# SenseBorgHAT.net
KiCad netlist of a schematic drawn in EAGLE
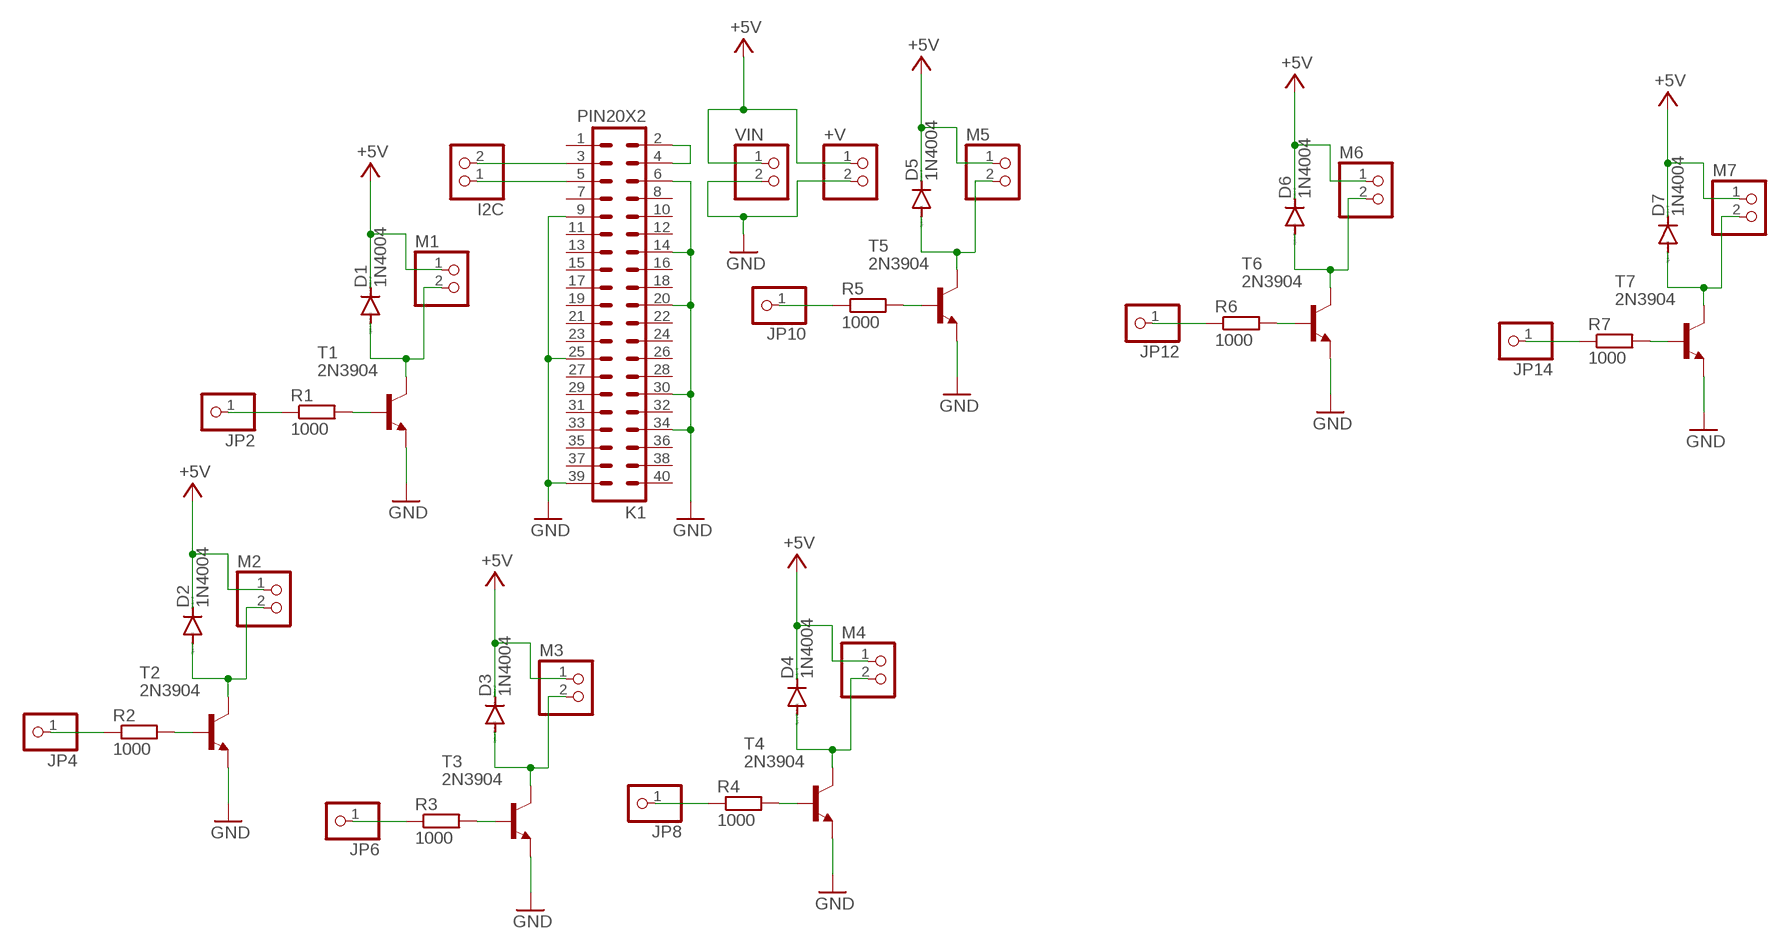
[diagram p0: schematic, sheet 1, part 1 of 2]
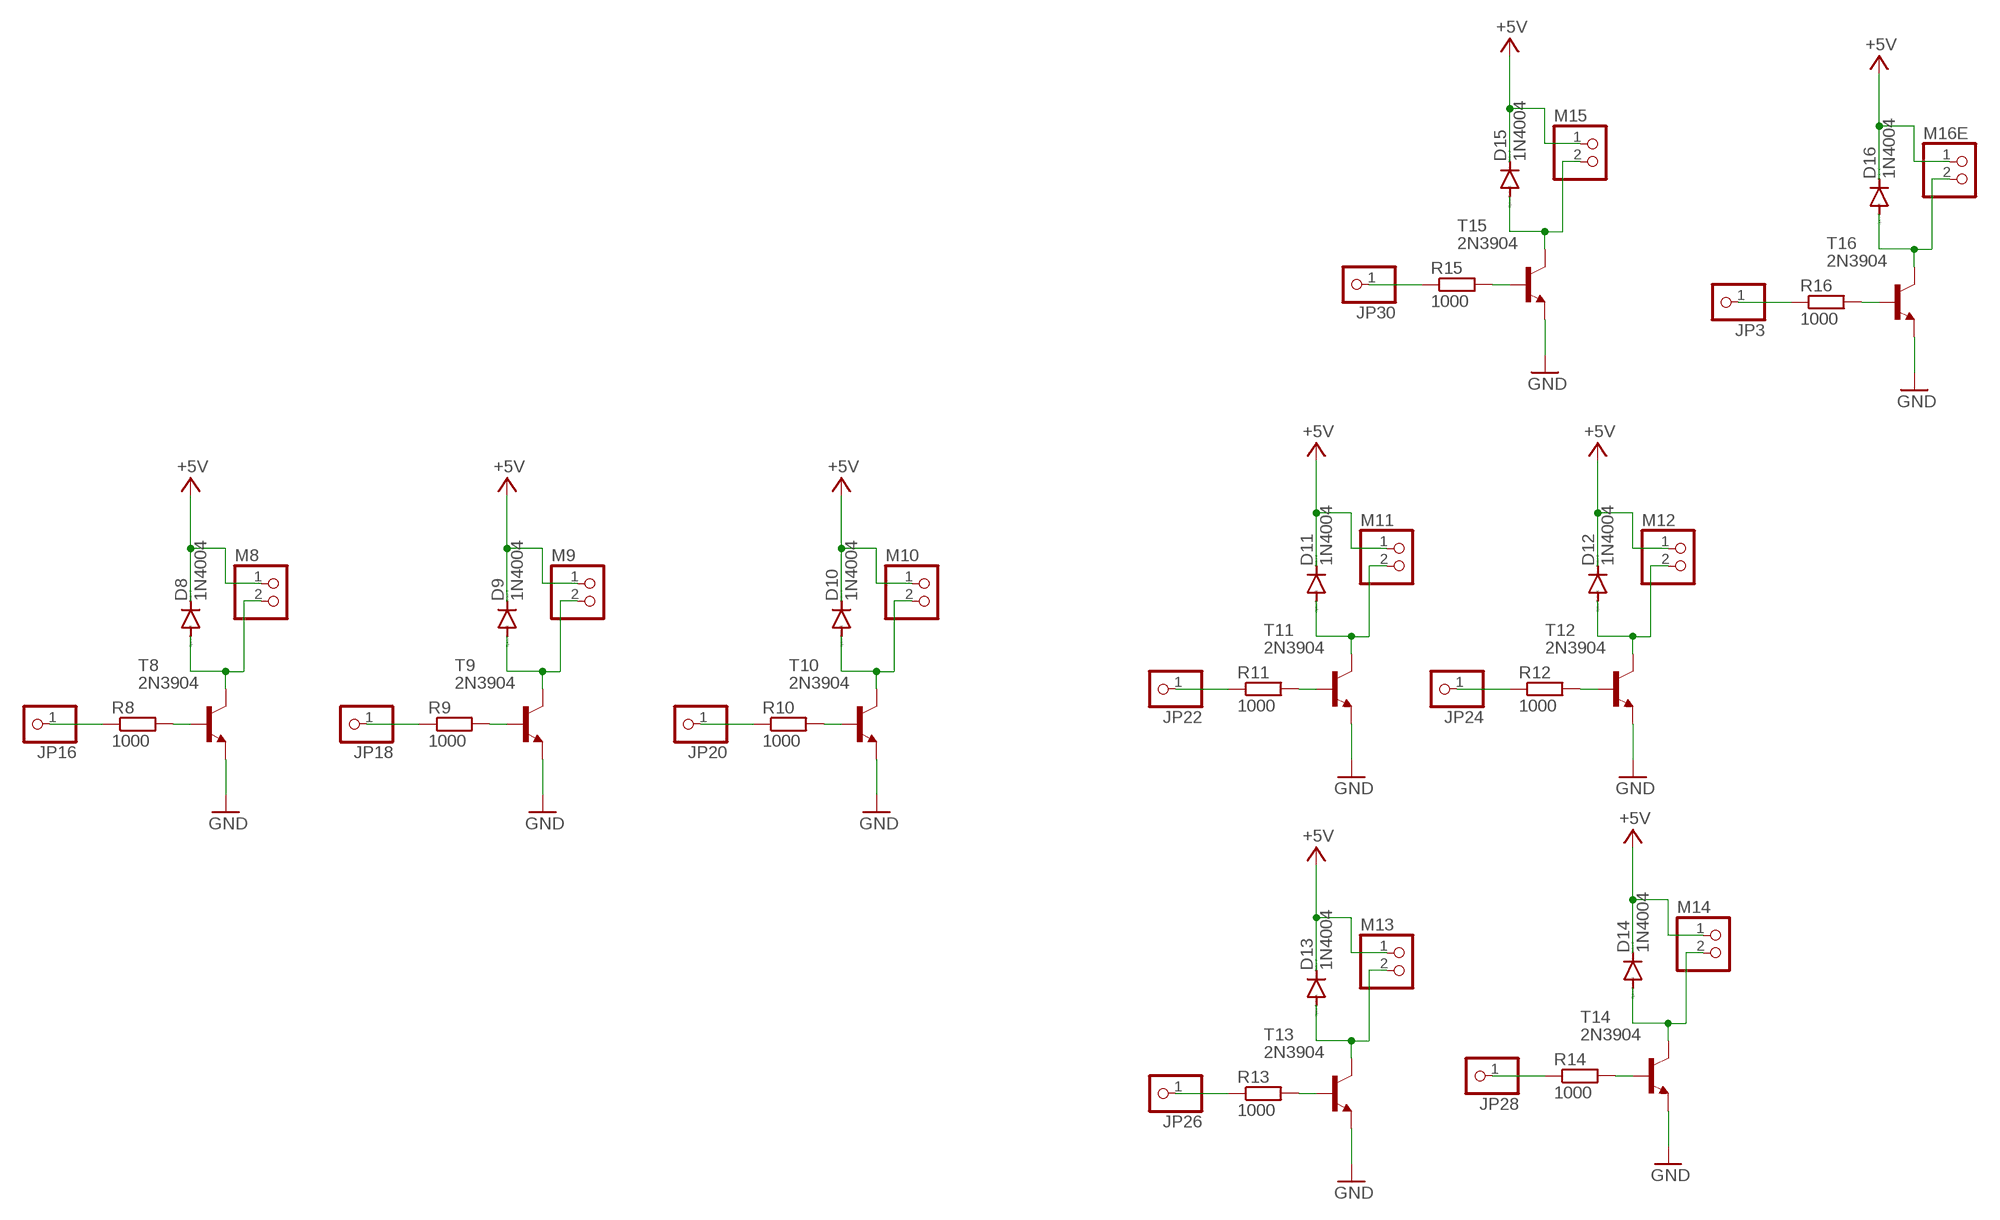
[diagram p1: schematic, sheet 1, part 2 of 2]

(export (version "E")
  (design (tool "Eeschema 10.0.6"))
  (components
    (comp (ref "+V")
      (value "PINHD-1X2")
      (footprint "eagle-import:1X02")
      (libsource (lib "eagle-import") (part "PINHD-1X2"))
    )
    (comp (ref "D1")
      (value "1N4004")
      (footprint "eagle-import:DO41-10")
      (libsource (lib "eagle-import") (part "1N4004"))
    )
    (comp (ref "D2")
      (value "1N4004")
      (footprint "eagle-import:DO41-10")
      (libsource (lib "eagle-import") (part "1N4004"))
    )
    (comp (ref "D3")
      (value "1N4004")
      (footprint "eagle-import:DO41-10")
      (libsource (lib "eagle-import") (part "1N4004"))
    )
    (comp (ref "D4")
      (value "1N4004")
      (footprint "eagle-import:DO41-10")
      (libsource (lib "eagle-import") (part "1N4004"))
    )
    (comp (ref "D5")
      (value "1N4004")
      (footprint "eagle-import:DO41-10")
      (libsource (lib "eagle-import") (part "1N4004"))
    )
    (comp (ref "D6")
      (value "1N4004")
      (footprint "eagle-import:DO41-10")
      (libsource (lib "eagle-import") (part "1N4004"))
    )
    (comp (ref "D7")
      (value "1N4004")
      (footprint "eagle-import:DO41-10")
      (libsource (lib "eagle-import") (part "1N4004"))
    )
    (comp (ref "D8")
      (value "1N4004")
      (footprint "eagle-import:DO41-10")
      (libsource (lib "eagle-import") (part "1N4004"))
    )
    (comp (ref "D9")
      (value "1N4004")
      (footprint "eagle-import:DO41-10")
      (libsource (lib "eagle-import") (part "1N4004"))
    )
    (comp (ref "D10")
      (value "1N4004")
      (footprint "eagle-import:DO41-10")
      (libsource (lib "eagle-import") (part "1N4004"))
    )
    (comp (ref "D11")
      (value "1N4004")
      (footprint "eagle-import:DO41-10")
      (libsource (lib "eagle-import") (part "1N4004"))
    )
    (comp (ref "D12")
      (value "1N4004")
      (footprint "eagle-import:DO41-10")
      (libsource (lib "eagle-import") (part "1N4004"))
    )
    (comp (ref "D13")
      (value "1N4004")
      (footprint "eagle-import:DO41-10")
      (libsource (lib "eagle-import") (part "1N4004"))
    )
    (comp (ref "D14")
      (value "1N4004")
      (footprint "eagle-import:DO41-10")
      (libsource (lib "eagle-import") (part "1N4004"))
    )
    (comp (ref "D15")
      (value "1N4004")
      (footprint "eagle-import:DO41-10")
      (libsource (lib "eagle-import") (part "1N4004"))
    )
    (comp (ref "D16")
      (value "1N4004")
      (footprint "eagle-import:DO41-10")
      (libsource (lib "eagle-import") (part "1N4004"))
    )
    (comp (ref "I2C")
      (value "PINHD-1X2")
      (footprint "eagle-import:1X02")
      (libsource (lib "eagle-import") (part "PINHD-1X2"))
    )
    (comp (ref "JP2")
      (value "PINHD-1X1")
      (footprint "eagle-import:1X01")
      (libsource (lib "eagle-import") (part "PINHD-1X1"))
    )
    (comp (ref "JP3")
      (value "PINHD-1X1")
      (footprint "eagle-import:1X01")
      (libsource (lib "eagle-import") (part "PINHD-1X1"))
    )
    (comp (ref "JP4")
      (value "PINHD-1X1")
      (footprint "eagle-import:1X01")
      (libsource (lib "eagle-import") (part "PINHD-1X1"))
    )
    (comp (ref "JP6")
      (value "PINHD-1X1")
      (footprint "eagle-import:1X01")
      (libsource (lib "eagle-import") (part "PINHD-1X1"))
    )
    (comp (ref "JP8")
      (value "PINHD-1X1")
      (footprint "eagle-import:1X01")
      (libsource (lib "eagle-import") (part "PINHD-1X1"))
    )
    (comp (ref "JP10")
      (value "PINHD-1X1")
      (footprint "eagle-import:1X01")
      (libsource (lib "eagle-import") (part "PINHD-1X1"))
    )
    (comp (ref "JP12")
      (value "PINHD-1X1")
      (footprint "eagle-import:1X01")
      (libsource (lib "eagle-import") (part "PINHD-1X1"))
    )
    (comp (ref "JP14")
      (value "PINHD-1X1")
      (footprint "eagle-import:1X01")
      (libsource (lib "eagle-import") (part "PINHD-1X1"))
    )
    (comp (ref "JP16")
      (value "PINHD-1X1")
      (footprint "eagle-import:1X01")
      (libsource (lib "eagle-import") (part "PINHD-1X1"))
    )
    (comp (ref "JP18")
      (value "PINHD-1X1")
      (footprint "eagle-import:1X01")
      (libsource (lib "eagle-import") (part "PINHD-1X1"))
    )
    (comp (ref "JP20")
      (value "PINHD-1X1")
      (footprint "eagle-import:1X01")
      (libsource (lib "eagle-import") (part "PINHD-1X1"))
    )
    (comp (ref "JP22")
      (value "PINHD-1X1")
      (footprint "eagle-import:1X01")
      (libsource (lib "eagle-import") (part "PINHD-1X1"))
    )
    (comp (ref "JP24")
      (value "PINHD-1X1")
      (footprint "eagle-import:1X01")
      (libsource (lib "eagle-import") (part "PINHD-1X1"))
    )
    (comp (ref "JP26")
      (value "PINHD-1X1")
      (footprint "eagle-import:1X01")
      (libsource (lib "eagle-import") (part "PINHD-1X1"))
    )
    (comp (ref "JP28")
      (value "PINHD-1X1")
      (footprint "eagle-import:1X01")
      (libsource (lib "eagle-import") (part "PINHD-1X1"))
    )
    (comp (ref "JP30")
      (value "PINHD-1X1")
      (footprint "eagle-import:1X01")
      (libsource (lib "eagle-import") (part "PINHD-1X1"))
    )
    (comp (ref "K1")
      (value "PIN20X2")
      (footprint "eagle-import:PIN_20X2")
      (libsource (lib "eagle-import") (part "PIN20X2"))
    )
    (comp (ref "M1")
      (value "PINHD-1X2")
      (footprint "eagle-import:1X02")
      (libsource (lib "eagle-import") (part "PINHD-1X2"))
    )
    (comp (ref "M2")
      (value "PINHD-1X2")
      (footprint "eagle-import:1X02")
      (libsource (lib "eagle-import") (part "PINHD-1X2"))
    )
    (comp (ref "M3")
      (value "PINHD-1X2")
      (footprint "eagle-import:1X02")
      (libsource (lib "eagle-import") (part "PINHD-1X2"))
    )
    (comp (ref "M4")
      (value "PINHD-1X2")
      (footprint "eagle-import:1X02")
      (libsource (lib "eagle-import") (part "PINHD-1X2"))
    )
    (comp (ref "M5")
      (value "PINHD-1X2")
      (footprint "eagle-import:1X02")
      (libsource (lib "eagle-import") (part "PINHD-1X2"))
    )
    (comp (ref "M6")
      (value "PINHD-1X2")
      (footprint "eagle-import:1X02")
      (libsource (lib "eagle-import") (part "PINHD-1X2"))
    )
    (comp (ref "M7")
      (value "PINHD-1X2")
      (footprint "eagle-import:1X02")
      (libsource (lib "eagle-import") (part "PINHD-1X2"))
    )
    (comp (ref "M8")
      (value "PINHD-1X2")
      (footprint "eagle-import:1X02")
      (libsource (lib "eagle-import") (part "PINHD-1X2"))
    )
    (comp (ref "M9")
      (value "PINHD-1X2")
      (footprint "eagle-import:1X02")
      (libsource (lib "eagle-import") (part "PINHD-1X2"))
    )
    (comp (ref "M10")
      (value "PINHD-1X2")
      (footprint "eagle-import:1X02")
      (libsource (lib "eagle-import") (part "PINHD-1X2"))
    )
    (comp (ref "M11")
      (value "PINHD-1X2")
      (footprint "eagle-import:1X02")
      (libsource (lib "eagle-import") (part "PINHD-1X2"))
    )
    (comp (ref "M12")
      (value "PINHD-1X2")
      (footprint "eagle-import:1X02")
      (libsource (lib "eagle-import") (part "PINHD-1X2"))
    )
    (comp (ref "M13")
      (value "PINHD-1X2")
      (footprint "eagle-import:1X02")
      (libsource (lib "eagle-import") (part "PINHD-1X2"))
    )
    (comp (ref "M14")
      (value "PINHD-1X2")
      (footprint "eagle-import:1X02")
      (libsource (lib "eagle-import") (part "PINHD-1X2"))
    )
    (comp (ref "M15")
      (value "PINHD-1X2")
      (footprint "eagle-import:1X02")
      (libsource (lib "eagle-import") (part "PINHD-1X2"))
    )
    (comp (ref "M16E")
      (value "PINHD-1X2")
      (footprint "eagle-import:1X02")
      (libsource (lib "eagle-import") (part "PINHD-1X2"))
    )
    (comp (ref "R1")
      (value "1000")
      (footprint "eagle-import:0207_10")
      (libsource (lib "eagle-import") (part "R-EU_0207/10"))
    )
    (comp (ref "R2")
      (value "1000")
      (footprint "eagle-import:0207_10")
      (libsource (lib "eagle-import") (part "R-EU_0207/10"))
    )
    (comp (ref "R3")
      (value "1000")
      (footprint "eagle-import:0207_10")
      (libsource (lib "eagle-import") (part "R-EU_0207/10"))
    )
    (comp (ref "R4")
      (value "1000")
      (footprint "eagle-import:0207_10")
      (libsource (lib "eagle-import") (part "R-EU_0207/10"))
    )
    (comp (ref "R5")
      (value "1000")
      (footprint "eagle-import:0207_10")
      (libsource (lib "eagle-import") (part "R-EU_0207/10"))
    )
    (comp (ref "R6")
      (value "1000")
      (footprint "eagle-import:0207_10")
      (libsource (lib "eagle-import") (part "R-EU_0207/10"))
    )
    (comp (ref "R7")
      (value "1000")
      (footprint "eagle-import:0207_10")
      (libsource (lib "eagle-import") (part "R-EU_0207/10"))
    )
    (comp (ref "R8")
      (value "1000")
      (footprint "eagle-import:0207_10")
      (libsource (lib "eagle-import") (part "R-EU_0207/10"))
    )
    (comp (ref "R9")
      (value "1000")
      (footprint "eagle-import:0207_10")
      (libsource (lib "eagle-import") (part "R-EU_0207/10"))
    )
    (comp (ref "R10")
      (value "1000")
      (footprint "eagle-import:0207_10")
      (libsource (lib "eagle-import") (part "R-EU_0207/10"))
    )
    (comp (ref "R11")
      (value "1000")
      (footprint "eagle-import:0207_10")
      (libsource (lib "eagle-import") (part "R-EU_0207/10"))
    )
    (comp (ref "R12")
      (value "1000")
      (footprint "eagle-import:0207_10")
      (libsource (lib "eagle-import") (part "R-EU_0207/10"))
    )
    (comp (ref "R13")
      (value "1000")
      (footprint "eagle-import:0207_10")
      (libsource (lib "eagle-import") (part "R-EU_0207/10"))
    )
    (comp (ref "R14")
      (value "1000")
      (footprint "eagle-import:0207_10")
      (libsource (lib "eagle-import") (part "R-EU_0207/10"))
    )
    (comp (ref "R15")
      (value "1000")
      (footprint "eagle-import:0207_10")
      (libsource (lib "eagle-import") (part "R-EU_0207/10"))
    )
    (comp (ref "R16")
      (value "1000")
      (footprint "eagle-import:0207_10")
      (libsource (lib "eagle-import") (part "R-EU_0207/10"))
    )
    (comp (ref "T1")
      (value "2N3904")
      (footprint "eagle-import:TO92")
      (libsource (lib "eagle-import") (part "2N3904"))
    )
    (comp (ref "T2")
      (value "2N3904")
      (footprint "eagle-import:TO92")
      (libsource (lib "eagle-import") (part "2N3904"))
    )
    (comp (ref "T3")
      (value "2N3904")
      (footprint "eagle-import:TO92")
      (libsource (lib "eagle-import") (part "2N3904"))
    )
    (comp (ref "T4")
      (value "2N3904")
      (footprint "eagle-import:TO92")
      (libsource (lib "eagle-import") (part "2N3904"))
    )
    (comp (ref "T5")
      (value "2N3904")
      (footprint "eagle-import:TO92")
      (libsource (lib "eagle-import") (part "2N3904"))
    )
    (comp (ref "T6")
      (value "2N3904")
      (footprint "eagle-import:TO92")
      (libsource (lib "eagle-import") (part "2N3904"))
    )
    (comp (ref "T7")
      (value "2N3904")
      (footprint "eagle-import:TO92")
      (libsource (lib "eagle-import") (part "2N3904"))
    )
    (comp (ref "T8")
      (value "2N3904")
      (footprint "eagle-import:TO92")
      (libsource (lib "eagle-import") (part "2N3904"))
    )
    (comp (ref "T9")
      (value "2N3904")
      (footprint "eagle-import:TO92")
      (libsource (lib "eagle-import") (part "2N3904"))
    )
    (comp (ref "T10")
      (value "2N3904")
      (footprint "eagle-import:TO92")
      (libsource (lib "eagle-import") (part "2N3904"))
    )
    (comp (ref "T11")
      (value "2N3904")
      (footprint "eagle-import:TO92")
      (libsource (lib "eagle-import") (part "2N3904"))
    )
    (comp (ref "T12")
      (value "2N3904")
      (footprint "eagle-import:TO92")
      (libsource (lib "eagle-import") (part "2N3904"))
    )
    (comp (ref "T13")
      (value "2N3904")
      (footprint "eagle-import:TO92")
      (libsource (lib "eagle-import") (part "2N3904"))
    )
    (comp (ref "T14")
      (value "2N3904")
      (footprint "eagle-import:TO92")
      (libsource (lib "eagle-import") (part "2N3904"))
    )
    (comp (ref "T15")
      (value "2N3904")
      (footprint "eagle-import:TO92")
      (libsource (lib "eagle-import") (part "2N3904"))
    )
    (comp (ref "T16")
      (value "2N3904")
      (footprint "eagle-import:TO92")
      (libsource (lib "eagle-import") (part "2N3904"))
    )
    (comp (ref "VIN")
      (value "PINHD-1X2")
      (footprint "eagle-import:1X02")
      (libsource (lib "eagle-import") (part "PINHD-1X2"))
    )
  )
  (nets
    (net (code "1") (name "+5V") (class "Default")
      (node (ref "+V") (pin "1") (pinfunction "1_1") (pintype "passive"))
      (node (ref "D1") (pin "C") (pinfunction "C_C") (pintype "passive"))
      (node (ref "D10") (pin "C") (pinfunction "C_C") (pintype "passive"))
      (node (ref "D11") (pin "C") (pinfunction "C_C") (pintype "passive"))
      (node (ref "D12") (pin "C") (pinfunction "C_C") (pintype "passive"))
      (node (ref "D13") (pin "C") (pinfunction "C_C") (pintype "passive"))
      (node (ref "D14") (pin "C") (pinfunction "C_C") (pintype "passive"))
      (node (ref "D15") (pin "C") (pinfunction "C_C") (pintype "passive"))
      (node (ref "D16") (pin "C") (pinfunction "C_C") (pintype "passive"))
      (node (ref "D2") (pin "C") (pinfunction "C_C") (pintype "passive"))
      (node (ref "D3") (pin "C") (pinfunction "C_C") (pintype "passive"))
      (node (ref "D4") (pin "C") (pinfunction "C_C") (pintype "passive"))
      (node (ref "D5") (pin "C") (pinfunction "C_C") (pintype "passive"))
      (node (ref "D6") (pin "C") (pinfunction "C_C") (pintype "passive"))
      (node (ref "D7") (pin "C") (pinfunction "C_C") (pintype "passive"))
      (node (ref "D8") (pin "C") (pinfunction "C_C") (pintype "passive"))
      (node (ref "D9") (pin "C") (pinfunction "C_C") (pintype "passive"))
      (node (ref "M1") (pin "1") (pinfunction "1_1") (pintype "passive"))
      (node (ref "M10") (pin "1") (pinfunction "1_1") (pintype "passive"))
      (node (ref "M11") (pin "1") (pinfunction "1_1") (pintype "passive"))
      (node (ref "M12") (pin "1") (pinfunction "1_1") (pintype "passive"))
      (node (ref "M13") (pin "1") (pinfunction "1_1") (pintype "passive"))
      (node (ref "M14") (pin "1") (pinfunction "1_1") (pintype "passive"))
      (node (ref "M15") (pin "1") (pinfunction "1_1") (pintype "passive"))
      (node (ref "M16E") (pin "1") (pinfunction "1_1") (pintype "passive"))
      (node (ref "M2") (pin "1") (pinfunction "1_1") (pintype "passive"))
      (node (ref "M3") (pin "1") (pinfunction "1_1") (pintype "passive"))
      (node (ref "M4") (pin "1") (pinfunction "1_1") (pintype "passive"))
      (node (ref "M5") (pin "1") (pinfunction "1_1") (pintype "passive"))
      (node (ref "M6") (pin "1") (pinfunction "1_1") (pintype "passive"))
      (node (ref "M7") (pin "1") (pinfunction "1_1") (pintype "passive"))
      (node (ref "M8") (pin "1") (pinfunction "1_1") (pintype "passive"))
      (node (ref "M9") (pin "1") (pinfunction "1_1") (pintype "passive"))
      (node (ref "VIN") (pin "1") (pinfunction "1_1") (pintype "passive"))
    )
    (net (code "2") (name "GND") (class "Default")
      (node (ref "+V") (pin "2") (pinfunction "2_2") (pintype "passive"))
      (node (ref "K1") (pin "14") (pinfunction "14_14") (pintype "passive"))
      (node (ref "K1") (pin "20") (pinfunction "20_20") (pintype "passive"))
      (node (ref "K1") (pin "25") (pinfunction "25_25") (pintype "passive"))
      (node (ref "K1") (pin "30") (pinfunction "30_30") (pintype "passive"))
      (node (ref "K1") (pin "34") (pinfunction "34_34") (pintype "passive"))
      (node (ref "K1") (pin "39") (pinfunction "39_39") (pintype "passive"))
      (node (ref "K1") (pin "6") (pinfunction "6_6") (pintype "passive"))
      (node (ref "K1") (pin "9") (pinfunction "9_9") (pintype "passive"))
      (node (ref "T1") (pin "3") (pinfunction "E_3") (pintype "passive"))
      (node (ref "T10") (pin "3") (pinfunction "E_3") (pintype "passive"))
      (node (ref "T11") (pin "3") (pinfunction "E_3") (pintype "passive"))
      (node (ref "T12") (pin "3") (pinfunction "E_3") (pintype "passive"))
      (node (ref "T13") (pin "3") (pinfunction "E_3") (pintype "passive"))
      (node (ref "T14") (pin "3") (pinfunction "E_3") (pintype "passive"))
      (node (ref "T15") (pin "3") (pinfunction "E_3") (pintype "passive"))
      (node (ref "T16") (pin "3") (pinfunction "E_3") (pintype "passive"))
      (node (ref "T2") (pin "3") (pinfunction "E_3") (pintype "passive"))
      (node (ref "T3") (pin "3") (pinfunction "E_3") (pintype "passive"))
      (node (ref "T4") (pin "3") (pinfunction "E_3") (pintype "passive"))
      (node (ref "T5") (pin "3") (pinfunction "E_3") (pintype "passive"))
      (node (ref "T6") (pin "3") (pinfunction "E_3") (pintype "passive"))
      (node (ref "T7") (pin "3") (pinfunction "E_3") (pintype "passive"))
      (node (ref "T8") (pin "3") (pinfunction "E_3") (pintype "passive"))
      (node (ref "T9") (pin "3") (pinfunction "E_3") (pintype "passive"))
      (node (ref "VIN") (pin "2") (pinfunction "2_2") (pintype "passive"))
    )
    (net (code "3") (name "Net-(I2C-Pad1)") (class "Default")
      (node (ref "I2C") (pin "1") (pinfunction "1_1") (pintype "passive"))
      (node (ref "K1") (pin "5") (pinfunction "5_5") (pintype "passive"))
    )
    (net (code "4") (name "Net-(I2C-Pad2)") (class "Default")
      (node (ref "I2C") (pin "2") (pinfunction "2_2") (pintype "passive"))
      (node (ref "K1") (pin "3") (pinfunction "3_3") (pintype "passive"))
    )
    (net (code "5") (name "Net-(JP2-Pad1)") (class "Default")
      (node (ref "JP2") (pin "1") (pinfunction "1_1") (pintype "passive"))
      (node (ref "R1") (pin "1") (pinfunction "1_1") (pintype "passive"))
    )
    (net (code "6") (name "Net-(JP3-Pad1)") (class "Default")
      (node (ref "JP3") (pin "1") (pinfunction "1_1") (pintype "passive"))
      (node (ref "R16") (pin "1") (pinfunction "1_1") (pintype "passive"))
    )
    (net (code "7") (name "Net-(JP4-Pad1)") (class "Default")
      (node (ref "JP4") (pin "1") (pinfunction "1_1") (pintype "passive"))
      (node (ref "R2") (pin "1") (pinfunction "1_1") (pintype "passive"))
    )
    (net (code "8") (name "Net-(JP6-Pad1)") (class "Default")
      (node (ref "JP6") (pin "1") (pinfunction "1_1") (pintype "passive"))
      (node (ref "R3") (pin "1") (pinfunction "1_1") (pintype "passive"))
    )
    (net (code "9") (name "Net-(JP8-Pad1)") (class "Default")
      (node (ref "JP8") (pin "1") (pinfunction "1_1") (pintype "passive"))
      (node (ref "R4") (pin "1") (pinfunction "1_1") (pintype "passive"))
    )
    (net (code "10") (name "Net-(JP10-Pad1)") (class "Default")
      (node (ref "JP10") (pin "1") (pinfunction "1_1") (pintype "passive"))
      (node (ref "R5") (pin "1") (pinfunction "1_1") (pintype "passive"))
    )
    (net (code "11") (name "Net-(JP12-Pad1)") (class "Default")
      (node (ref "JP12") (pin "1") (pinfunction "1_1") (pintype "passive"))
      (node (ref "R6") (pin "1") (pinfunction "1_1") (pintype "passive"))
    )
    (net (code "12") (name "Net-(JP14-Pad1)") (class "Default")
      (node (ref "JP14") (pin "1") (pinfunction "1_1") (pintype "passive"))
      (node (ref "R7") (pin "1") (pinfunction "1_1") (pintype "passive"))
    )
    (net (code "13") (name "Net-(JP16-Pad1)") (class "Default")
      (node (ref "JP16") (pin "1") (pinfunction "1_1") (pintype "passive"))
      (node (ref "R8") (pin "1") (pinfunction "1_1") (pintype "passive"))
    )
    (net (code "14") (name "Net-(JP18-Pad1)") (class "Default")
      (node (ref "JP18") (pin "1") (pinfunction "1_1") (pintype "passive"))
      (node (ref "R9") (pin "1") (pinfunction "1_1") (pintype "passive"))
    )
    (net (code "15") (name "Net-(JP20-Pad1)") (class "Default")
      (node (ref "JP20") (pin "1") (pinfunction "1_1") (pintype "passive"))
      (node (ref "R10") (pin "1") (pinfunction "1_1") (pintype "passive"))
    )
    (net (code "16") (name "Net-(JP22-Pad1)") (class "Default")
      (node (ref "JP22") (pin "1") (pinfunction "1_1") (pintype "passive"))
      (node (ref "R11") (pin "1") (pinfunction "1_1") (pintype "passive"))
    )
    (net (code "17") (name "Net-(JP24-Pad1)") (class "Default")
      (node (ref "JP24") (pin "1") (pinfunction "1_1") (pintype "passive"))
      (node (ref "R12") (pin "1") (pinfunction "1_1") (pintype "passive"))
    )
    (net (code "18") (name "Net-(JP26-Pad1)") (class "Default")
      (node (ref "JP26") (pin "1") (pinfunction "1_1") (pintype "passive"))
      (node (ref "R13") (pin "1") (pinfunction "1_1") (pintype "passive"))
    )
    (net (code "19") (name "Net-(JP28-Pad1)") (class "Default")
      (node (ref "JP28") (pin "1") (pinfunction "1_1") (pintype "passive"))
      (node (ref "R14") (pin "1") (pinfunction "1_1") (pintype "passive"))
    )
    (net (code "20") (name "Net-(JP30-Pad1)") (class "Default")
      (node (ref "JP30") (pin "1") (pinfunction "1_1") (pintype "passive"))
      (node (ref "R15") (pin "1") (pinfunction "1_1") (pintype "passive"))
    )
    (net (code "21") (name "Net-(K1-Pad2)") (class "Default")
      (node (ref "K1") (pin "2") (pinfunction "2_2") (pintype "passive"))
      (node (ref "K1") (pin "4") (pinfunction "4_4") (pintype "passive"))
    )
    (net (code "22") (name "Net-(T1-B)") (class "Default")
      (node (ref "R1") (pin "2") (pinfunction "2_2") (pintype "passive"))
      (node (ref "T1") (pin "2") (pinfunction "B_2") (pintype "passive"))
    )
    (net (code "23") (name "Net-(T1-C)") (class "Default")
      (node (ref "D1") (pin "A") (pinfunction "A_A") (pintype "passive"))
      (node (ref "M1") (pin "2") (pinfunction "2_2") (pintype "passive"))
      (node (ref "T1") (pin "1") (pinfunction "C_1") (pintype "passive"))
    )
    (net (code "24") (name "Net-(T2-B)") (class "Default")
      (node (ref "R2") (pin "2") (pinfunction "2_2") (pintype "passive"))
      (node (ref "T2") (pin "2") (pinfunction "B_2") (pintype "passive"))
    )
    (net (code "25") (name "Net-(T2-C)") (class "Default")
      (node (ref "D2") (pin "A") (pinfunction "A_A") (pintype "passive"))
      (node (ref "M2") (pin "2") (pinfunction "2_2") (pintype "passive"))
      (node (ref "T2") (pin "1") (pinfunction "C_1") (pintype "passive"))
    )
    (net (code "26") (name "Net-(T3-B)") (class "Default")
      (node (ref "R3") (pin "2") (pinfunction "2_2") (pintype "passive"))
      (node (ref "T3") (pin "2") (pinfunction "B_2") (pintype "passive"))
    )
    (net (code "27") (name "Net-(T3-C)") (class "Default")
      (node (ref "D3") (pin "A") (pinfunction "A_A") (pintype "passive"))
      (node (ref "M3") (pin "2") (pinfunction "2_2") (pintype "passive"))
      (node (ref "T3") (pin "1") (pinfunction "C_1") (pintype "passive"))
    )
    (net (code "28") (name "Net-(T4-B)") (class "Default")
      (node (ref "R4") (pin "2") (pinfunction "2_2") (pintype "passive"))
      (node (ref "T4") (pin "2") (pinfunction "B_2") (pintype "passive"))
    )
    (net (code "29") (name "Net-(T4-C)") (class "Default")
      (node (ref "D4") (pin "A") (pinfunction "A_A") (pintype "passive"))
      (node (ref "M4") (pin "2") (pinfunction "2_2") (pintype "passive"))
      (node (ref "T4") (pin "1") (pinfunction "C_1") (pintype "passive"))
    )
    (net (code "30") (name "Net-(T5-B)") (class "Default")
      (node (ref "R5") (pin "2") (pinfunction "2_2") (pintype "passive"))
      (node (ref "T5") (pin "2") (pinfunction "B_2") (pintype "passive"))
    )
    (net (code "31") (name "Net-(T5-C)") (class "Default")
      (node (ref "D5") (pin "A") (pinfunction "A_A") (pintype "passive"))
      (node (ref "M5") (pin "2") (pinfunction "2_2") (pintype "passive"))
      (node (ref "T5") (pin "1") (pinfunction "C_1") (pintype "passive"))
    )
    (net (code "32") (name "Net-(T6-B)") (class "Default")
      (node (ref "R6") (pin "2") (pinfunction "2_2") (pintype "passive"))
      (node (ref "T6") (pin "2") (pinfunction "B_2") (pintype "passive"))
    )
    (net (code "33") (name "Net-(T6-C)") (class "Default")
      (node (ref "D6") (pin "A") (pinfunction "A_A") (pintype "passive"))
      (node (ref "M6") (pin "2") (pinfunction "2_2") (pintype "passive"))
      (node (ref "T6") (pin "1") (pinfunction "C_1") (pintype "passive"))
    )
    (net (code "34") (name "Net-(T7-B)") (class "Default")
      (node (ref "R7") (pin "2") (pinfunction "2_2") (pintype "passive"))
      (node (ref "T7") (pin "2") (pinfunction "B_2") (pintype "passive"))
    )
    (net (code "35") (name "Net-(T7-C)") (class "Default")
      (node (ref "D7") (pin "A") (pinfunction "A_A") (pintype "passive"))
      (node (ref "M7") (pin "2") (pinfunction "2_2") (pintype "passive"))
      (node (ref "T7") (pin "1") (pinfunction "C_1") (pintype "passive"))
    )
    (net (code "36") (name "Net-(T8-B)") (class "Default")
      (node (ref "R8") (pin "2") (pinfunction "2_2") (pintype "passive"))
      (node (ref "T8") (pin "2") (pinfunction "B_2") (pintype "passive"))
    )
    (net (code "37") (name "Net-(T8-C)") (class "Default")
      (node (ref "D8") (pin "A") (pinfunction "A_A") (pintype "passive"))
      (node (ref "M8") (pin "2") (pinfunction "2_2") (pintype "passive"))
      (node (ref "T8") (pin "1") (pinfunction "C_1") (pintype "passive"))
    )
    (net (code "38") (name "Net-(T9-B)") (class "Default")
      (node (ref "R9") (pin "2") (pinfunction "2_2") (pintype "passive"))
      (node (ref "T9") (pin "2") (pinfunction "B_2") (pintype "passive"))
    )
    (net (code "39") (name "Net-(T9-C)") (class "Default")
      (node (ref "D9") (pin "A") (pinfunction "A_A") (pintype "passive"))
      (node (ref "M9") (pin "2") (pinfunction "2_2") (pintype "passive"))
      (node (ref "T9") (pin "1") (pinfunction "C_1") (pintype "passive"))
    )
    (net (code "40") (name "Net-(T10-B)") (class "Default")
      (node (ref "R10") (pin "2") (pinfunction "2_2") (pintype "passive"))
      (node (ref "T10") (pin "2") (pinfunction "B_2") (pintype "passive"))
    )
    (net (code "41") (name "Net-(T10-C)") (class "Default")
      (node (ref "D10") (pin "A") (pinfunction "A_A") (pintype "passive"))
      (node (ref "M10") (pin "2") (pinfunction "2_2") (pintype "passive"))
      (node (ref "T10") (pin "1") (pinfunction "C_1") (pintype "passive"))
    )
    (net (code "42") (name "Net-(T11-B)") (class "Default")
      (node (ref "R11") (pin "2") (pinfunction "2_2") (pintype "passive"))
      (node (ref "T11") (pin "2") (pinfunction "B_2") (pintype "passive"))
    )
    (net (code "43") (name "Net-(T11-C)") (class "Default")
      (node (ref "D11") (pin "A") (pinfunction "A_A") (pintype "passive"))
      (node (ref "M11") (pin "2") (pinfunction "2_2") (pintype "passive"))
      (node (ref "T11") (pin "1") (pinfunction "C_1") (pintype "passive"))
    )
    (net (code "44") (name "Net-(T12-B)") (class "Default")
      (node (ref "R12") (pin "2") (pinfunction "2_2") (pintype "passive"))
      (node (ref "T12") (pin "2") (pinfunction "B_2") (pintype "passive"))
    )
    (net (code "45") (name "Net-(T12-C)") (class "Default")
      (node (ref "D12") (pin "A") (pinfunction "A_A") (pintype "passive"))
      (node (ref "M12") (pin "2") (pinfunction "2_2") (pintype "passive"))
      (node (ref "T12") (pin "1") (pinfunction "C_1") (pintype "passive"))
    )
    (net (code "46") (name "Net-(T13-B)") (class "Default")
      (node (ref "R13") (pin "2") (pinfunction "2_2") (pintype "passive"))
      (node (ref "T13") (pin "2") (pinfunction "B_2") (pintype "passive"))
    )
    (net (code "47") (name "Net-(T13-C)") (class "Default")
      (node (ref "D13") (pin "A") (pinfunction "A_A") (pintype "passive"))
      (node (ref "M13") (pin "2") (pinfunction "2_2") (pintype "passive"))
      (node (ref "T13") (pin "1") (pinfunction "C_1") (pintype "passive"))
    )
    (net (code "48") (name "Net-(T14-B)") (class "Default")
      (node (ref "R14") (pin "2") (pinfunction "2_2") (pintype "passive"))
      (node (ref "T14") (pin "2") (pinfunction "B_2") (pintype "passive"))
    )
    (net (code "49") (name "Net-(T14-C)") (class "Default")
      (node (ref "D14") (pin "A") (pinfunction "A_A") (pintype "passive"))
      (node (ref "M14") (pin "2") (pinfunction "2_2") (pintype "passive"))
      (node (ref "T14") (pin "1") (pinfunction "C_1") (pintype "passive"))
    )
    (net (code "50") (name "Net-(T15-B)") (class "Default")
      (node (ref "R15") (pin "2") (pinfunction "2_2") (pintype "passive"))
      (node (ref "T15") (pin "2") (pinfunction "B_2") (pintype "passive"))
    )
    (net (code "51") (name "Net-(T15-C)") (class "Default")
      (node (ref "D15") (pin "A") (pinfunction "A_A") (pintype "passive"))
      (node (ref "M15") (pin "2") (pinfunction "2_2") (pintype "passive"))
      (node (ref "T15") (pin "1") (pinfunction "C_1") (pintype "passive"))
    )
    (net (code "52") (name "Net-(T16-B)") (class "Default")
      (node (ref "R16") (pin "2") (pinfunction "2_2") (pintype "passive"))
      (node (ref "T16") (pin "2") (pinfunction "B_2") (pintype "passive"))
    )
    (net (code "53") (name "Net-(T16-C)") (class "Default")
      (node (ref "D16") (pin "A") (pinfunction "A_A") (pintype "passive"))
      (node (ref "M16E") (pin "2") (pinfunction "2_2") (pintype "passive"))
      (node (ref "T16") (pin "1") (pinfunction "C_1") (pintype "passive"))
    )
    (net (code "54") (name "unconnected-(K1-Pad1)") (class "Default")
      (node (ref "K1") (pin "1") (pinfunction "1_1") (pintype "passive"))
    )
    (net (code "55") (name "unconnected-(K1-Pad7)") (class "Default")
      (node (ref "K1") (pin "7") (pinfunction "7_7") (pintype "passive"))
    )
    (net (code "56") (name "unconnected-(K1-Pad8)") (class "Default")
      (node (ref "K1") (pin "8") (pinfunction "8_8") (pintype "passive"))
    )
    (net (code "57") (name "unconnected-(K1-Pad10)") (class "Default")
      (node (ref "K1") (pin "10") (pinfunction "10_10") (pintype "passive"))
    )
    (net (code "58") (name "unconnected-(K1-Pad11)") (class "Default")
      (node (ref "K1") (pin "11") (pinfunction "11_11") (pintype "passive"))
    )
    (net (code "59") (name "unconnected-(K1-Pad12)") (class "Default")
      (node (ref "K1") (pin "12") (pinfunction "12_12") (pintype "passive"))
    )
    (net (code "60") (name "unconnected-(K1-Pad13)") (class "Default")
      (node (ref "K1") (pin "13") (pinfunction "13_13") (pintype "passive"))
    )
    (net (code "61") (name "unconnected-(K1-Pad15)") (class "Default")
      (node (ref "K1") (pin "15") (pinfunction "15_15") (pintype "passive"))
    )
    (net (code "62") (name "unconnected-(K1-Pad16)") (class "Default")
      (node (ref "K1") (pin "16") (pinfunction "16_16") (pintype "passive"))
    )
    (net (code "63") (name "unconnected-(K1-Pad17)") (class "Default")
      (node (ref "K1") (pin "17") (pinfunction "17_17") (pintype "passive"))
    )
    (net (code "64") (name "unconnected-(K1-Pad18)") (class "Default")
      (node (ref "K1") (pin "18") (pinfunction "18_18") (pintype "passive"))
    )
    (net (code "65") (name "unconnected-(K1-Pad19)") (class "Default")
      (node (ref "K1") (pin "19") (pinfunction "19_19") (pintype "passive"))
    )
    (net (code "66") (name "unconnected-(K1-Pad21)") (class "Default")
      (node (ref "K1") (pin "21") (pinfunction "21_21") (pintype "passive"))
    )
    (net (code "67") (name "unconnected-(K1-Pad22)") (class "Default")
      (node (ref "K1") (pin "22") (pinfunction "22_22") (pintype "passive"))
    )
    (net (code "68") (name "unconnected-(K1-Pad23)") (class "Default")
      (node (ref "K1") (pin "23") (pinfunction "23_23") (pintype "passive"))
    )
    (net (code "69") (name "unconnected-(K1-Pad24)") (class "Default")
      (node (ref "K1") (pin "24") (pinfunction "24_24") (pintype "passive"))
    )
    (net (code "70") (name "unconnected-(K1-Pad26)") (class "Default")
      (node (ref "K1") (pin "26") (pinfunction "26_26") (pintype "passive"))
    )
    (net (code "71") (name "unconnected-(K1-Pad27)") (class "Default")
      (node (ref "K1") (pin "27") (pinfunction "27_27") (pintype "passive"))
    )
    (net (code "72") (name "unconnected-(K1-Pad28)") (class "Default")
      (node (ref "K1") (pin "28") (pinfunction "28_28") (pintype "passive"))
    )
    (net (code "73") (name "unconnected-(K1-Pad29)") (class "Default")
      (node (ref "K1") (pin "29") (pinfunction "29_29") (pintype "passive"))
    )
    (net (code "74") (name "unconnected-(K1-Pad31)") (class "Default")
      (node (ref "K1") (pin "31") (pinfunction "31_31") (pintype "passive"))
    )
    (net (code "75") (name "unconnected-(K1-Pad32)") (class "Default")
      (node (ref "K1") (pin "32") (pinfunction "32_32") (pintype "passive"))
    )
    (net (code "76") (name "unconnected-(K1-Pad33)") (class "Default")
      (node (ref "K1") (pin "33") (pinfunction "33_33") (pintype "passive"))
    )
    (net (code "77") (name "unconnected-(K1-Pad35)") (class "Default")
      (node (ref "K1") (pin "35") (pinfunction "35_35") (pintype "passive"))
    )
    (net (code "78") (name "unconnected-(K1-Pad36)") (class "Default")
      (node (ref "K1") (pin "36") (pinfunction "36_36") (pintype "passive"))
    )
    (net (code "79") (name "unconnected-(K1-Pad37)") (class "Default")
      (node (ref "K1") (pin "37") (pinfunction "37_37") (pintype "passive"))
    )
    (net (code "80") (name "unconnected-(K1-Pad38)") (class "Default")
      (node (ref "K1") (pin "38") (pinfunction "38_38") (pintype "passive"))
    )
    (net (code "81") (name "unconnected-(K1-Pad40)") (class "Default")
      (node (ref "K1") (pin "40") (pinfunction "40_40") (pintype "passive"))
    )
  )
)
